# converter.net
KiCad netlist of a schematic drawn in EAGLE
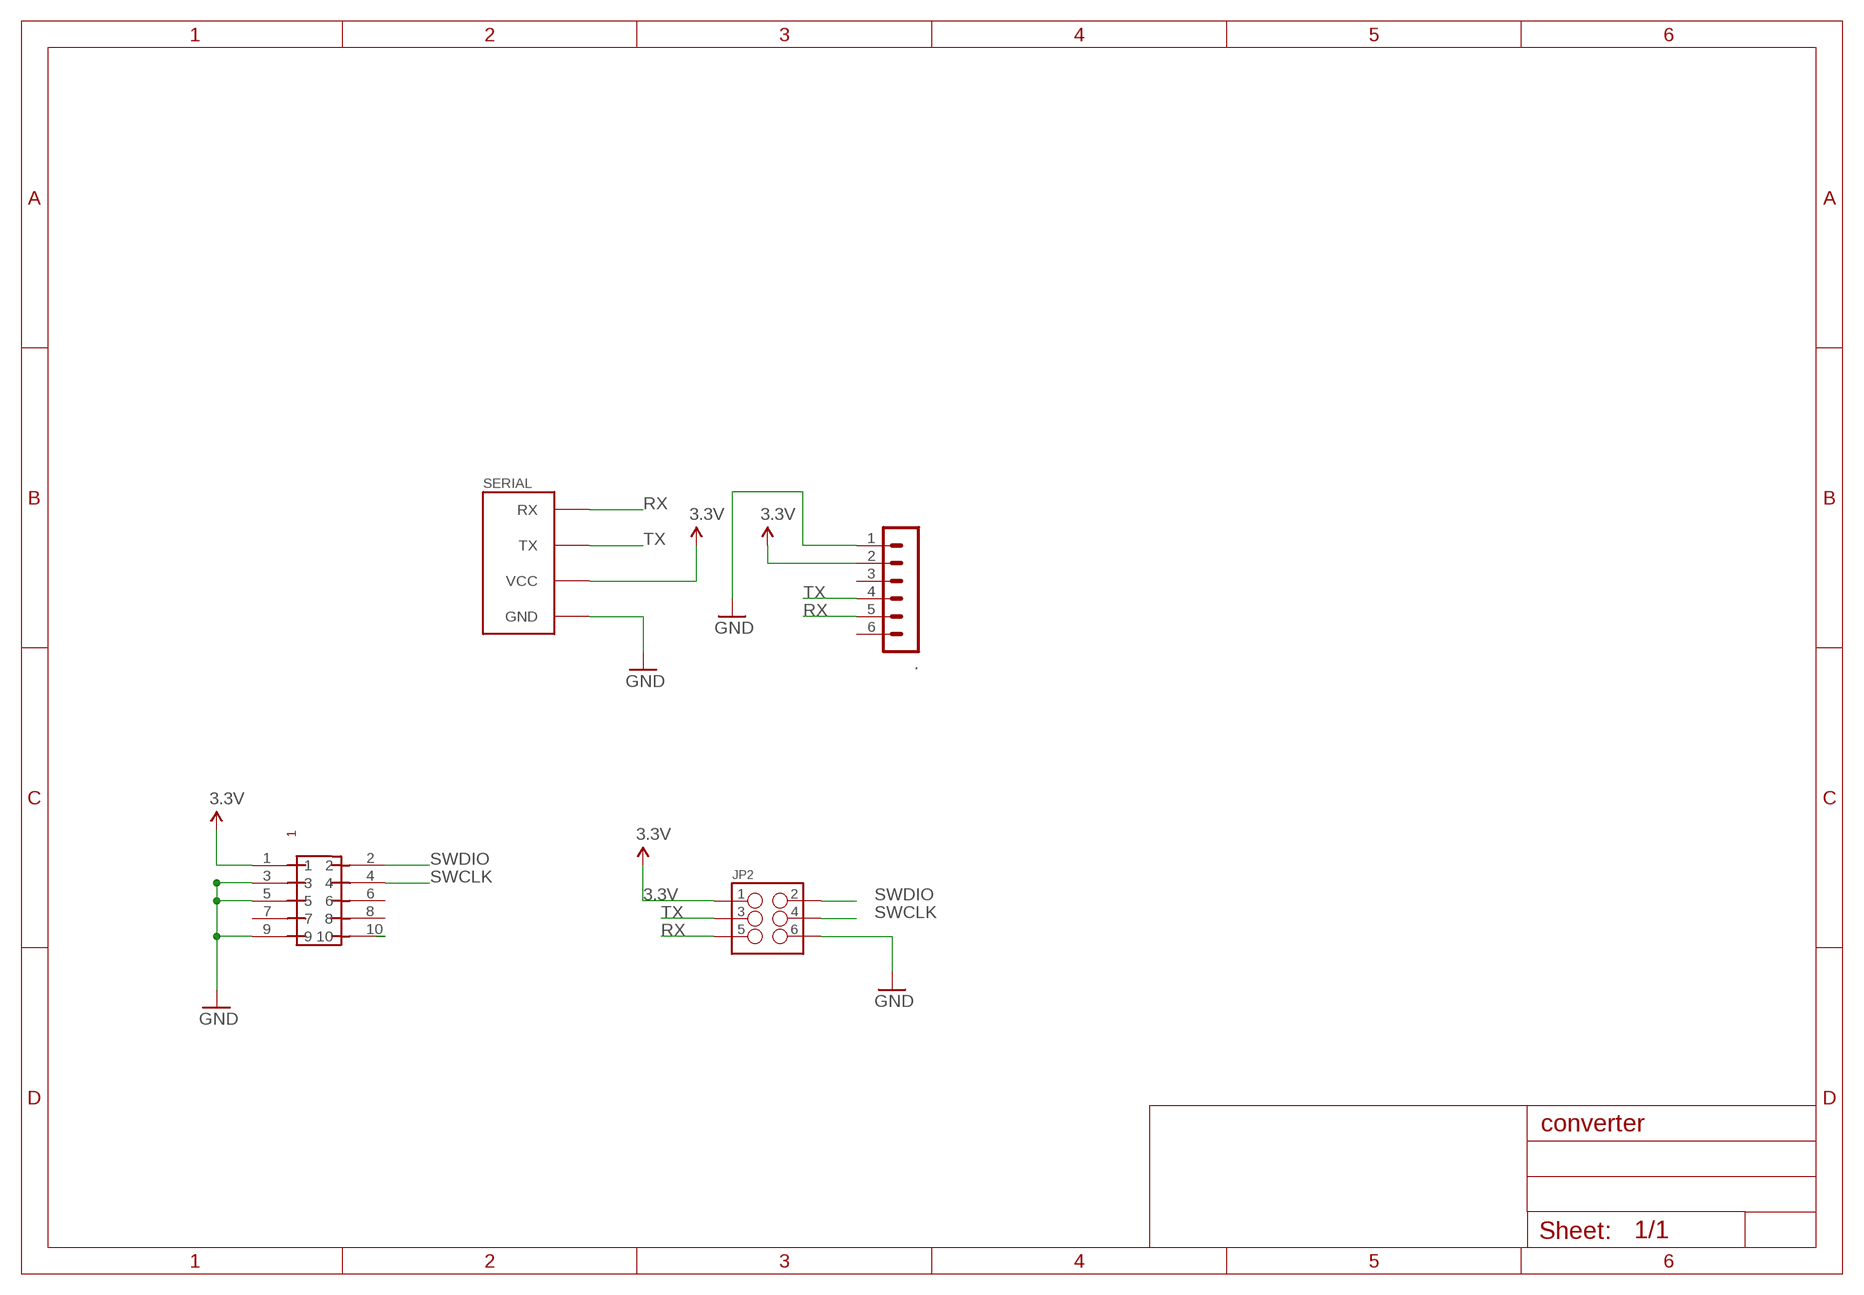
[diagram p0: schematic, sheet 1]

(export (version "E")
  (design (tool "Eeschema 10.0.6"))
  (components
    (comp (ref ".")
      (value "MA06-1")
      (footprint "eagle-import:MA06-1")
      (libsource (lib "eagle-import") (part "MA06-1"))
    )
    (comp (ref "JP2")
      (value "M03X2")
      (footprint "eagle-import:2X3-SHROUDED")
      (libsource (lib "eagle-import") (part "M03X2"))
    )
    (comp (ref "SERIAL")
      (value "FABO_BRICK_SERIAL-CONNECTOR_I")
      (footprint "eagle-import:FABO_BRICK_SERIAL_CONNECTOR_I")
      (libsource (lib "eagle-import") (part "FABO_BRICK_SERIAL-CONNECTOR_I"))
    )
    (comp (ref "U$5")
      (value "PIN-HEADER-SMT(1.27MM)2X5")
      (footprint "eagle-import:PIN-HEADER-SMT(1.27MM)2X5")
      (libsource (lib "eagle-import") (part "PIN-HEADER-SMT(1.27MM)2X5"))
    )
  )
  (nets
    (net (code "1") (name "/RX") (class "Default")
      (node (ref ".") (pin "5") (pinfunction "5_5") (pintype "passive"))
      (node (ref "JP2") (pin "5") (pinfunction "5_5") (pintype "bidirectional"))
      (node (ref "SERIAL") (pin "RX") (pinfunction "RX_RX") (pintype "bidirectional"))
    )
    (net (code "2") (name "/SWCLK") (class "Default")
      (node (ref "JP2") (pin "4") (pinfunction "4_4") (pintype "bidirectional"))
      (node (ref "U$5") (pin "4") (pinfunction "4_4") (pintype "bidirectional"))
    )
    (net (code "3") (name "/SWDIO") (class "Default")
      (node (ref "JP2") (pin "2") (pinfunction "2_2") (pintype "bidirectional"))
      (node (ref "U$5") (pin "2") (pinfunction "2_2") (pintype "bidirectional"))
    )
    (net (code "4") (name "/TX") (class "Default")
      (node (ref ".") (pin "4") (pinfunction "4_4") (pintype "passive"))
      (node (ref "JP2") (pin "3") (pinfunction "3_3") (pintype "bidirectional"))
      (node (ref "SERIAL") (pin "TX") (pinfunction "TX_TX") (pintype "bidirectional"))
    )
    (net (code "5") (name "3.3V") (class "Default")
      (node (ref ".") (pin "2") (pinfunction "2_2") (pintype "passive"))
      (node (ref "JP2") (pin "1") (pinfunction "1_1") (pintype "bidirectional"))
      (node (ref "SERIAL") (pin "VCC") (pinfunction "VCC_VCC") (pintype "bidirectional"))
      (node (ref "U$5") (pin "1") (pinfunction "1_1") (pintype "bidirectional"))
    )
    (net (code "6") (name "GND") (class "Default")
      (node (ref ".") (pin "1") (pinfunction "1_1") (pintype "passive"))
      (node (ref "JP2") (pin "6") (pinfunction "6_6") (pintype "bidirectional"))
      (node (ref "SERIAL") (pin "GND") (pinfunction "GND_GND") (pintype "bidirectional"))
      (node (ref "U$5") (pin "3") (pinfunction "3_3") (pintype "bidirectional"))
      (node (ref "U$5") (pin "5") (pinfunction "5_5") (pintype "bidirectional"))
      (node (ref "U$5") (pin "9") (pinfunction "9_9") (pintype "bidirectional"))
    )
    (net (code "7") (name "unconnected-(.-Pad3)") (class "Default")
      (node (ref ".") (pin "3") (pinfunction "3_3") (pintype "passive"))
    )
    (net (code "8") (name "unconnected-(.-Pad6)") (class "Default")
      (node (ref ".") (pin "6") (pinfunction "6_6") (pintype "passive"))
    )
    (net (code "9") (name "unconnected-(U$5-Pad6)") (class "Default")
      (node (ref "U$5") (pin "6") (pinfunction "6_6") (pintype "bidirectional"))
    )
    (net (code "10") (name "unconnected-(U$5-Pad7)") (class "Default")
      (node (ref "U$5") (pin "7") (pinfunction "7_7") (pintype "bidirectional"))
    )
    (net (code "11") (name "unconnected-(U$5-Pad8)") (class "Default")
      (node (ref "U$5") (pin "8") (pinfunction "8_8") (pintype "bidirectional"))
    )
    (net (code "12") (name "unconnected-(U$5-Pad10)") (class "Default")
      (node (ref "U$5") (pin "10") (pinfunction "10_10") (pintype "bidirectional"))
    )
  )
)
